# Seven-Seg_Displays.net
KiCad netlist of a schematic drawn in Altium Designer
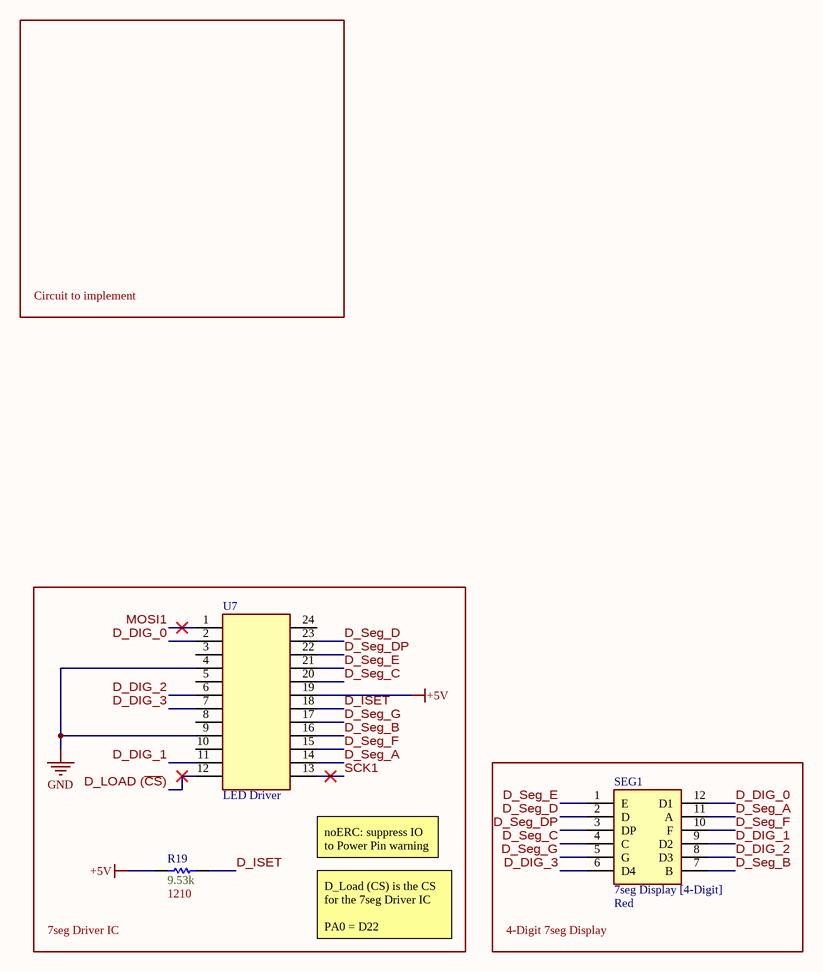
[diagram p0: Seven-Seg Displays.SchDoc]

(export (version "E")
  (design (tool "Eeschema 10.0.6"))
  (components
    (comp (ref "R19")
      (value "SMD Resistor")
      (footprint "SMD Resistor [1210]")
      (description "JLC Part #: C728401\r\n(for 1M Ohm Res)")
      (fields
        (field (name "JLC PART #") "C728401")
        (field (name "MOUSER PART #") "ERJ-14NF9531U")
        (field (name "RESISTANCE") "9.53k")
        (field (name "SIZE PACKAGE") "1210")
      )
      (libsource (lib "RADM Components") (part "SMD Resistor"))
    )
    (comp (ref "SEG1")
      (value "7seg Display [4-Digit]")
      (footprint "7seg Display [4 Digit]")
      (fields (field (name "MOUSER PART #") "474-COM-11405") (field (name "COLOR") "Red"))
      (libsource (lib "RADM Components") (part "7seg Display [4-Digit]"))
    )
    (comp (ref "U7")
      (value "LED Driver")
      (footprint "DIP IC [24pin, IC]")
      (fields (field (name "MOUSER PART #") "700-MAX7219ENG"))
      (libsource (lib "RADM Components") (part "DIP IC [24pin]"))
    )
  )
  (nets
    (net (code "1") (name "+5V") (class "Default")
      (node (ref "R19") (pin "1") (pinfunction "1_1") (pintype "passive"))
      (node (ref "U7") (pin "19") (pinfunction "V+_19") (pintype "power_in"))
    )
    (net (code "2") (name "/D_DIG_0") (class "Default")
      (node (ref "SEG1") (pin "12") (pinfunction "D1_12") (pintype "power_in"))
      (node (ref "U7") (pin "2") (pinfunction "DIG0_2") (pintype "power_in"))
    )
    (net (code "3") (name "/D_DIG_1") (class "Default")
      (node (ref "SEG1") (pin "9") (pinfunction "D2_9") (pintype "power_in"))
      (node (ref "U7") (pin "11") (pinfunction "DIG1_11") (pintype "power_in"))
    )
    (net (code "4") (name "/D_DIG_2") (class "Default")
      (node (ref "SEG1") (pin "8") (pinfunction "D3_8") (pintype "power_in"))
      (node (ref "U7") (pin "6") (pinfunction "DIG2_6") (pintype "power_in"))
    )
    (net (code "5") (name "/D_DIG_3") (class "Default")
      (node (ref "SEG1") (pin "6") (pinfunction "D4_6") (pintype "power_in"))
      (node (ref "U7") (pin "7") (pinfunction "DIG3_7") (pintype "power_in"))
    )
    (net (code "6") (name "/D_ISET") (class "Default")
      (node (ref "R19") (pin "2") (pinfunction "2_2") (pintype "passive"))
      (node (ref "U7") (pin "18") (pinfunction "ISET_18") (pintype "power_in"))
    )
    (net (code "7") (name "/D_LOAD (~{CS})") (class "Default")
      (node (ref "U7") (pin "12") (pinfunction "LOAD_(~{CS})_12") (pintype "power_in+no_connect"))
    )
    (net (code "8") (name "/D_Seg_A") (class "Default")
      (node (ref "SEG1") (pin "11") (pinfunction "A_11") (pintype "power_in"))
      (node (ref "U7") (pin "14") (pinfunction "SEGA_14") (pintype "power_in"))
    )
    (net (code "9") (name "/D_Seg_B") (class "Default")
      (node (ref "SEG1") (pin "7") (pinfunction "B_7") (pintype "power_in"))
      (node (ref "U7") (pin "16") (pinfunction "SEGB_16") (pintype "power_in"))
    )
    (net (code "10") (name "/D_Seg_C") (class "Default")
      (node (ref "SEG1") (pin "4") (pinfunction "C_4") (pintype "power_in"))
      (node (ref "U7") (pin "20") (pinfunction "SEGC_20") (pintype "power_in"))
    )
    (net (code "11") (name "/D_Seg_D") (class "Default")
      (node (ref "SEG1") (pin "2") (pinfunction "D_2") (pintype "power_in"))
      (node (ref "U7") (pin "23") (pinfunction "SEGD_23") (pintype "power_in"))
    )
    (net (code "12") (name "/D_Seg_DP") (class "Default")
      (node (ref "SEG1") (pin "3") (pinfunction "DP_3") (pintype "power_in"))
      (node (ref "U7") (pin "22") (pinfunction "SEGDP_22") (pintype "power_in"))
    )
    (net (code "13") (name "/D_Seg_E") (class "Default")
      (node (ref "SEG1") (pin "1") (pinfunction "E_1") (pintype "power_in"))
      (node (ref "U7") (pin "21") (pinfunction "SEGE_21") (pintype "power_in"))
    )
    (net (code "14") (name "/D_Seg_F") (class "Default")
      (node (ref "SEG1") (pin "10") (pinfunction "F_10") (pintype "power_in"))
      (node (ref "U7") (pin "15") (pinfunction "SEGF_15") (pintype "power_in"))
    )
    (net (code "15") (name "/D_Seg_G") (class "Default")
      (node (ref "SEG1") (pin "5") (pinfunction "G_5") (pintype "power_in"))
      (node (ref "U7") (pin "17") (pinfunction "SEGG_17") (pintype "power_in"))
    )
    (net (code "16") (name "/MOSI1") (class "Default")
      (node (ref "U7") (pin "1") (pinfunction "DIN_1") (pintype "power_in"))
    )
    (net (code "17") (name "/SCK1") (class "Default")
      (node (ref "U7") (pin "13") (pinfunction "CLK_13") (pintype "power_in"))
    )
    (net (code "18") (name "GND") (class "Default")
      (node (ref "U7") (pin "4") (pinfunction "GND_4") (pintype "power_in"))
      (node (ref "U7") (pin "9") (pinfunction "GND_9") (pintype "power_in"))
    )
    (net (code "19") (name "unconnected-(U7-DIG4-Pad3)") (class "Default")
      (node (ref "U7") (pin "3") (pinfunction "DIG4_3") (pintype "power_in"))
    )
    (net (code "20") (name "unconnected-(U7-DIG5-Pad10)") (class "Default")
      (node (ref "U7") (pin "10") (pinfunction "DIG5_10") (pintype "power_in"))
    )
    (net (code "21") (name "unconnected-(U7-DIG6-Pad5)") (class "Default")
      (node (ref "U7") (pin "5") (pinfunction "DIG6_5") (pintype "power_in"))
    )
    (net (code "22") (name "unconnected-(U7-DIG7-Pad8)") (class "Default")
      (node (ref "U7") (pin "8") (pinfunction "DIG7_8") (pintype "power_in"))
    )
    (net (code "23") (name "unconnected-(U7-DOUT-Pad24)") (class "Default")
      (node (ref "U7") (pin "24") (pinfunction "DOUT_24") (pintype "power_in"))
    )
  )
)
